# mini-v1_5-moving-parts.net
KiCad netlist of a schematic drawn in EAGLE
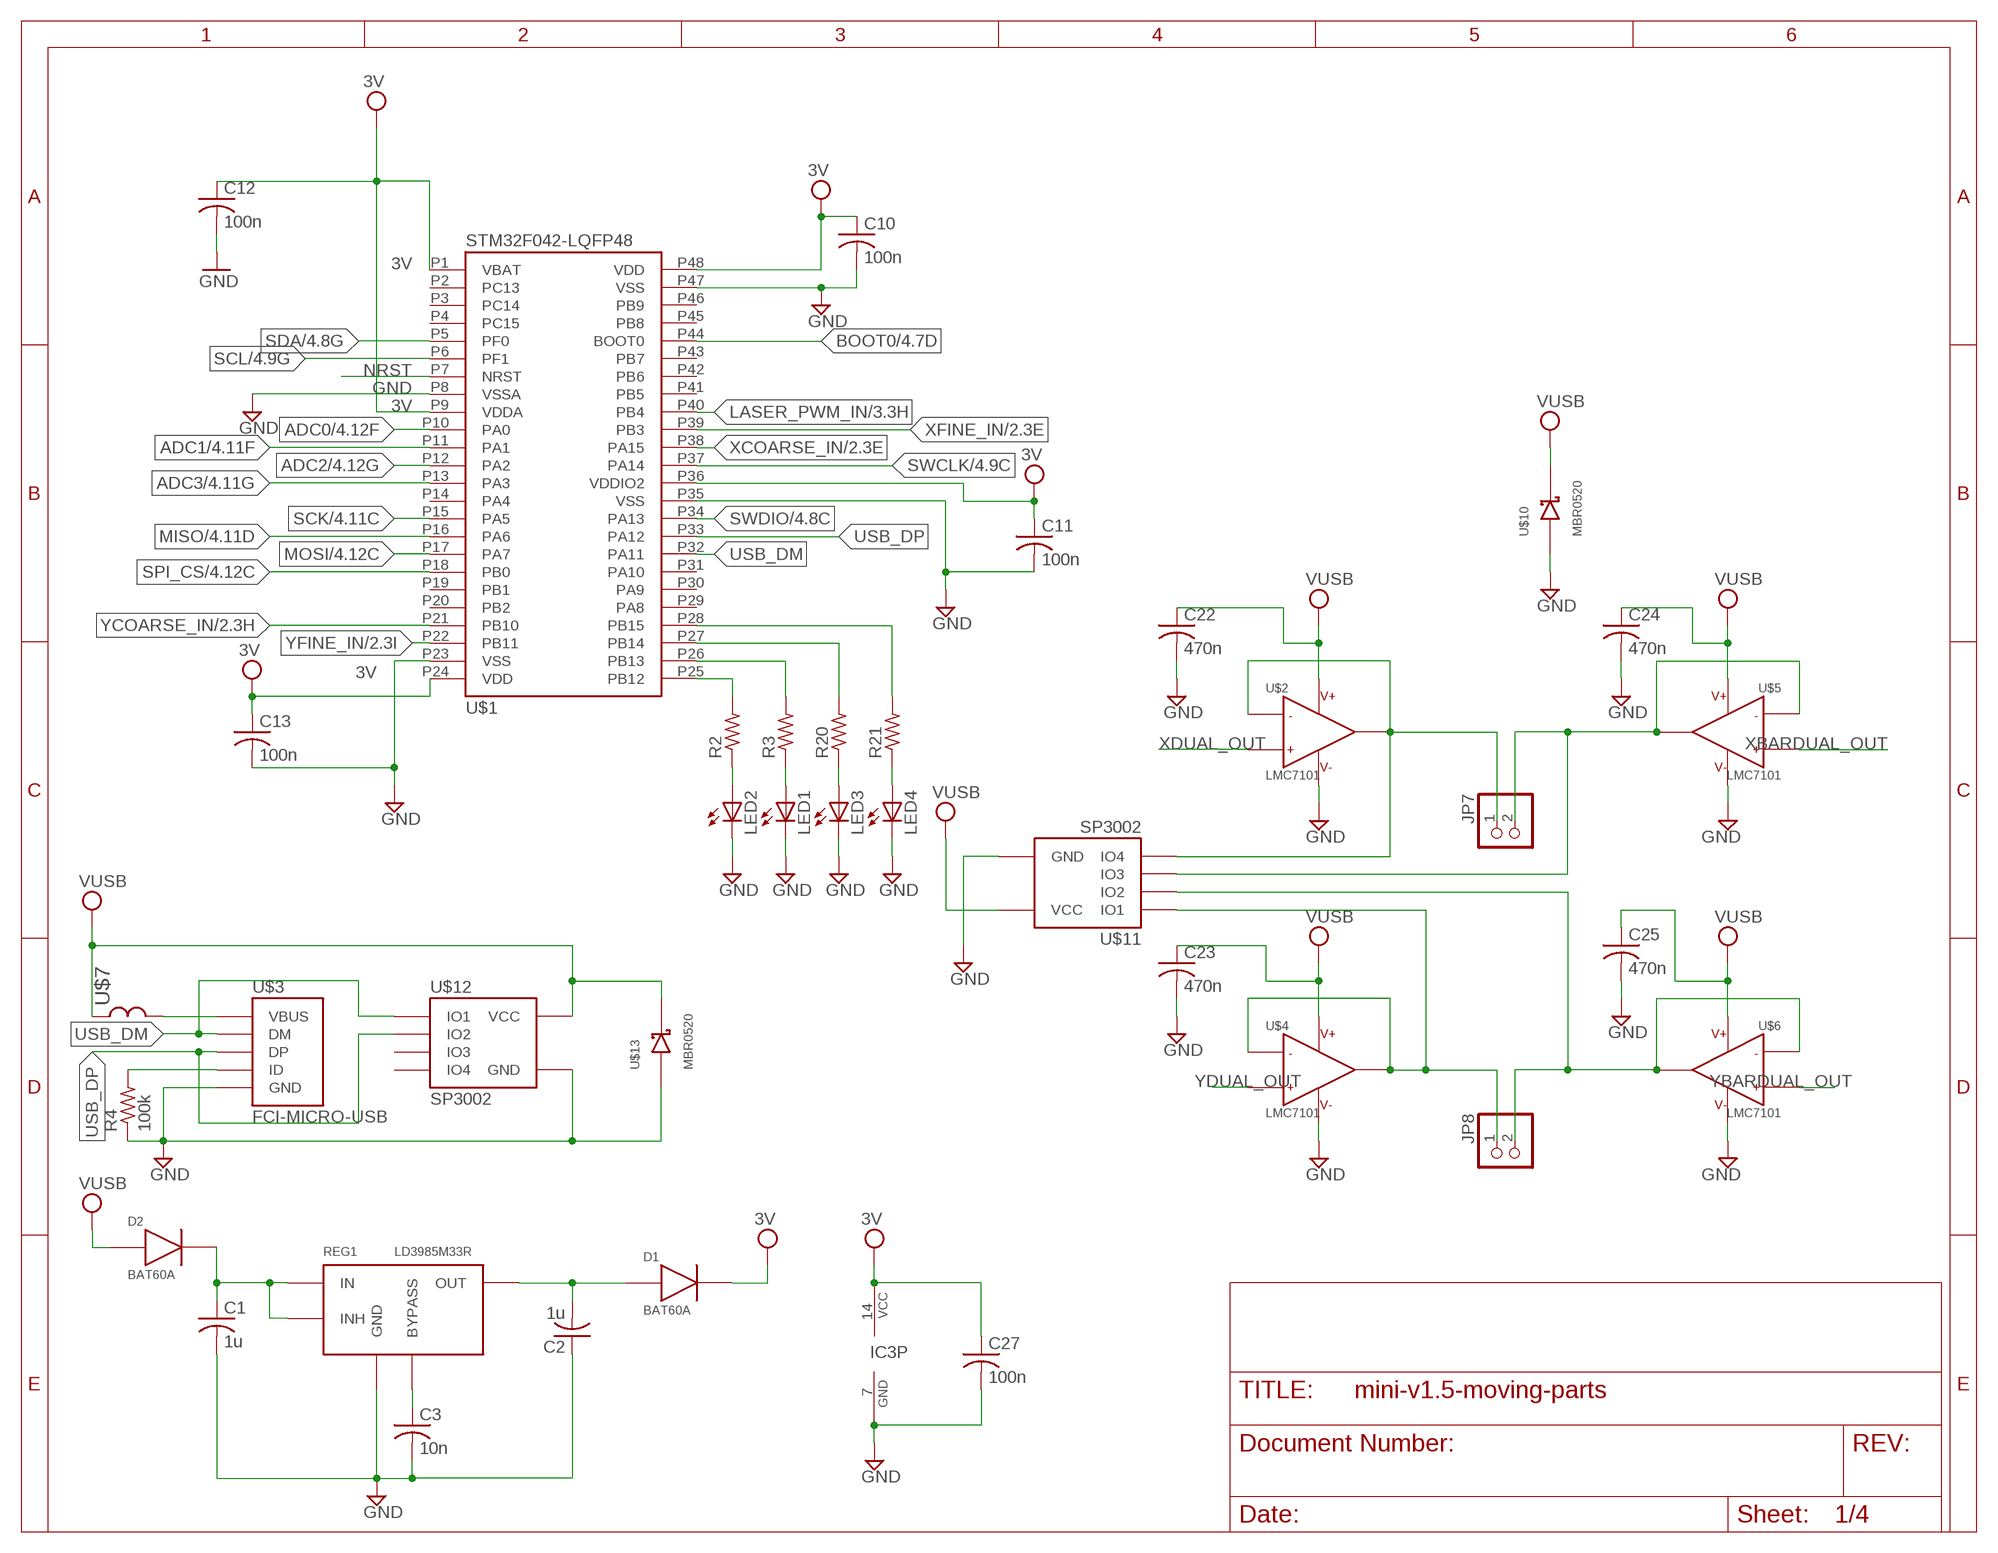
[diagram p0: schematic, sheet 1]
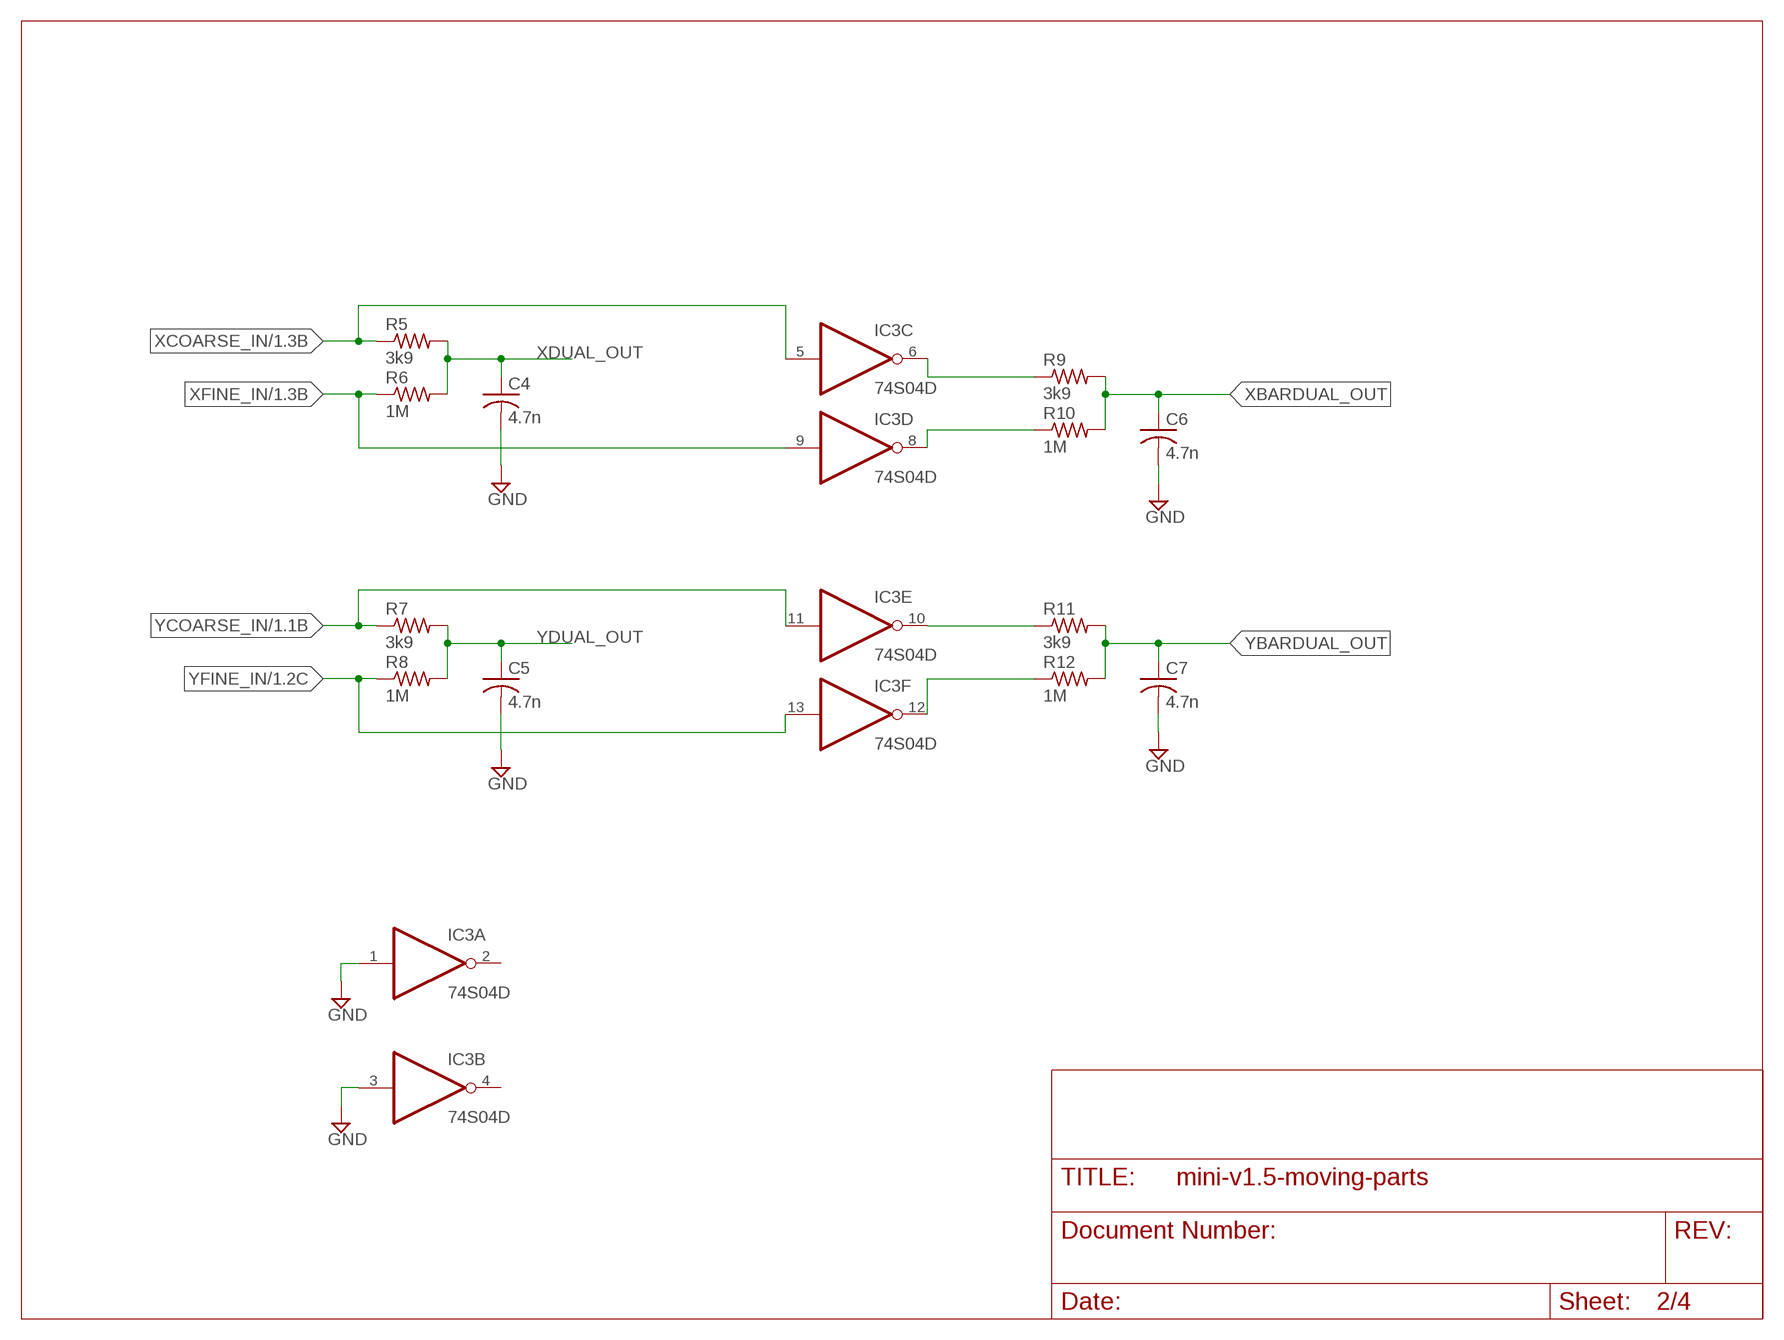
[diagram p1: schematic, sheet 2]
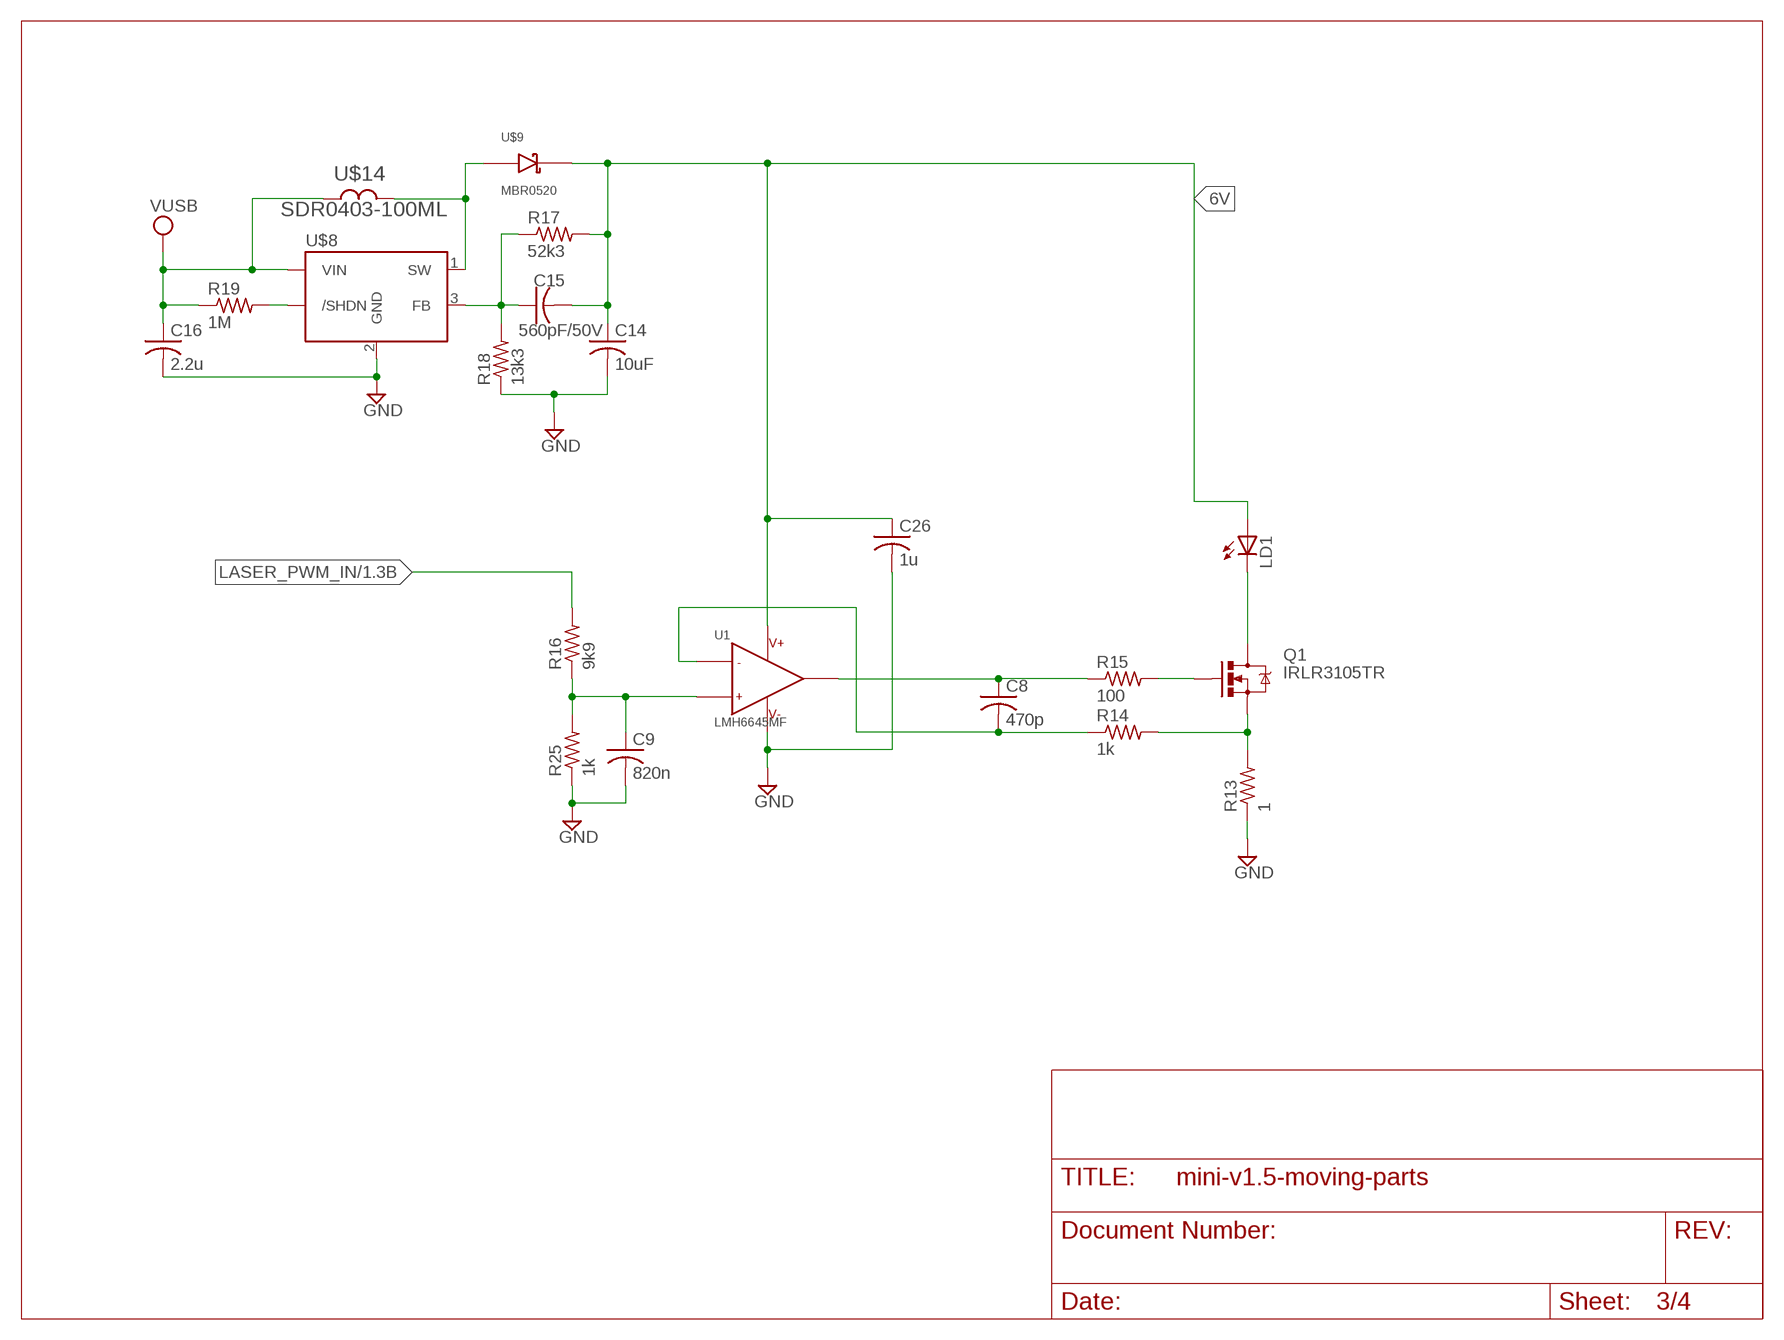
[diagram p2: schematic, sheet 3]
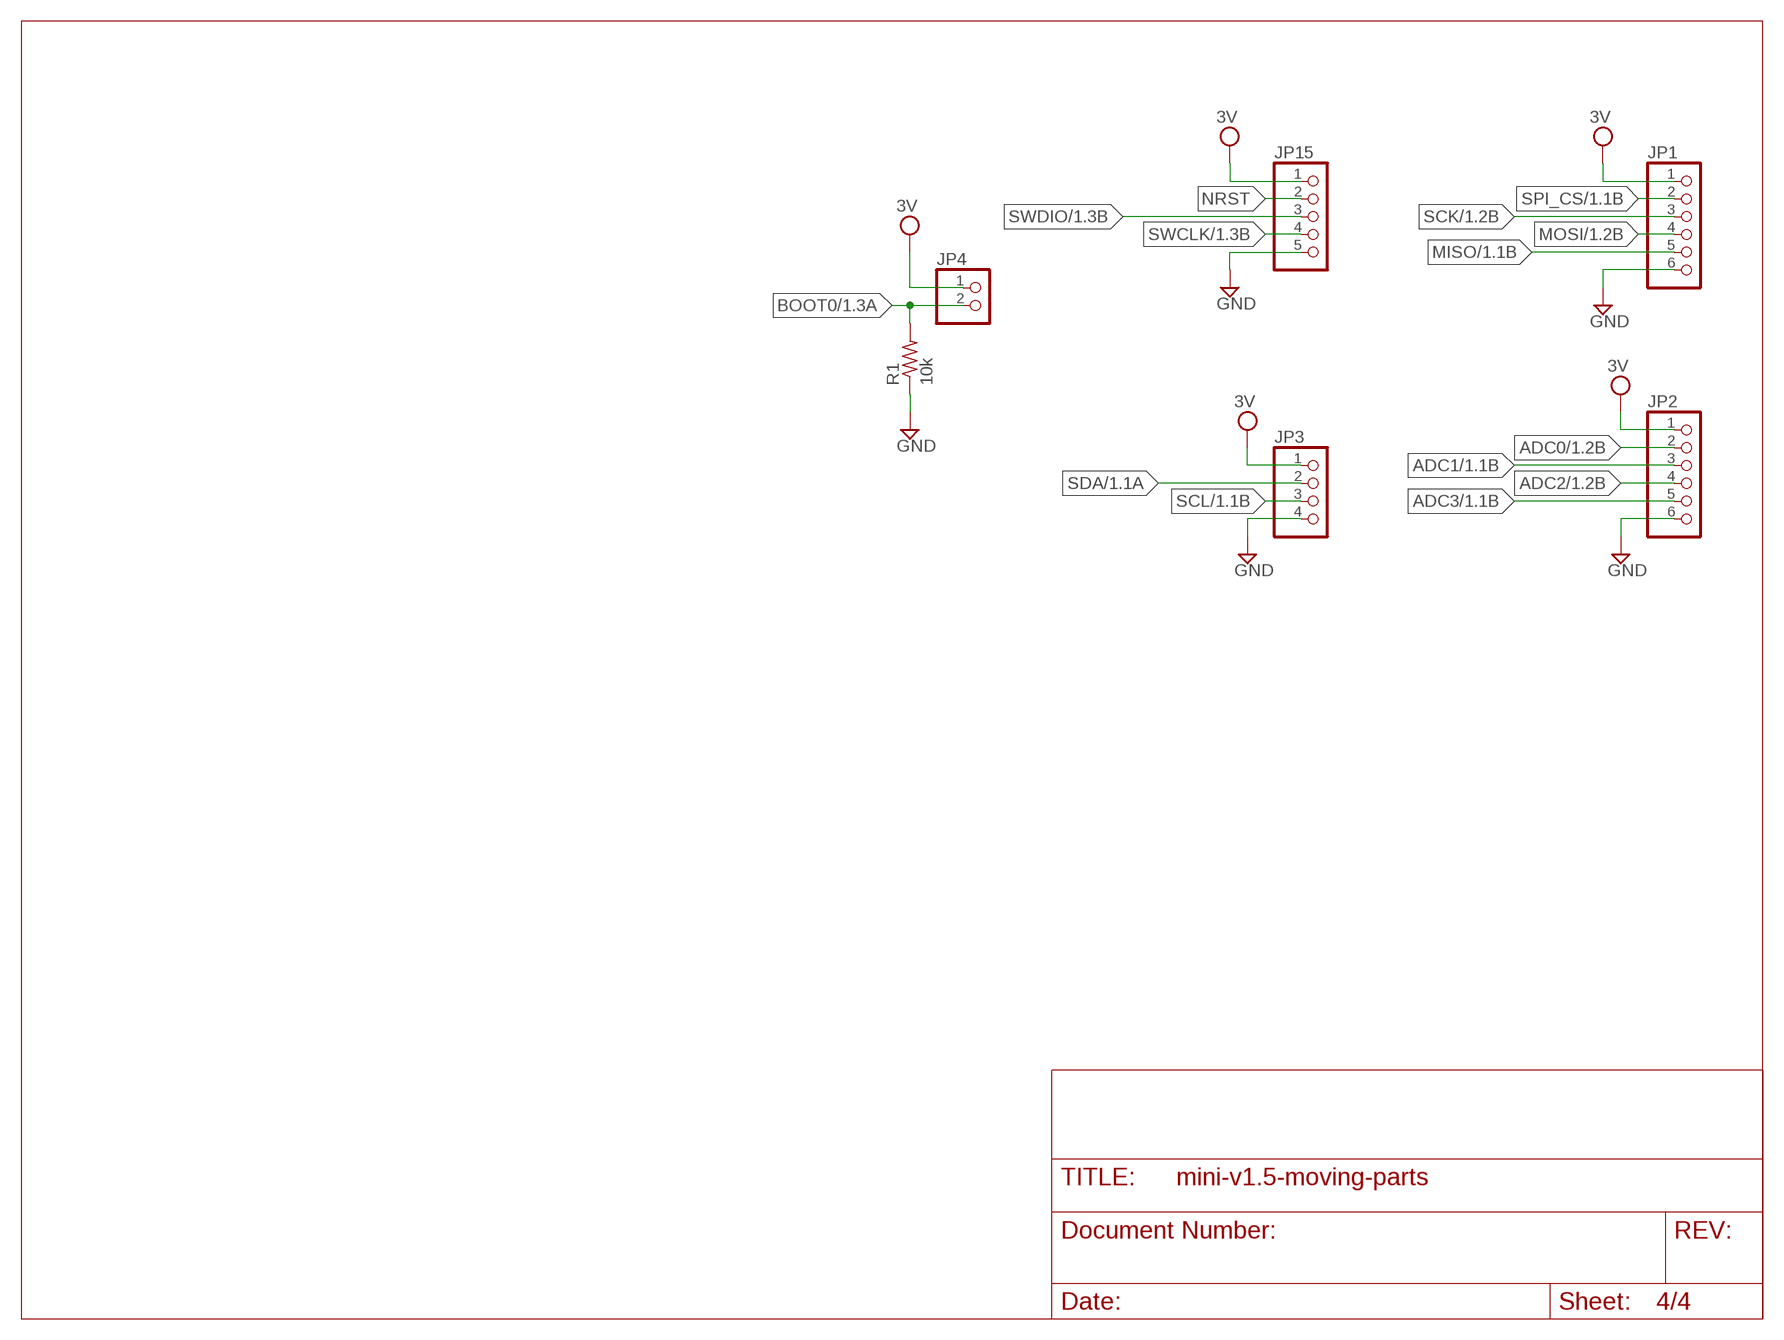
[diagram p3: schematic, sheet 4]

(export (version "E")
  (design (tool "Eeschema 10.0.6"))
  (components
    (comp (ref "C1")
      (value "1u")
      (footprint "eagle-import:C0603")
      (libsource (lib "eagle-import") (part "C-USC0603"))
    )
    (comp (ref "C2")
      (value "1u")
      (footprint "eagle-import:C0603")
      (libsource (lib "eagle-import") (part "C-USC0603"))
    )
    (comp (ref "C3")
      (value "10n")
      (footprint "eagle-import:C0603")
      (libsource (lib "eagle-import") (part "C-USC0603"))
    )
    (comp (ref "C10")
      (value "100n")
      (footprint "eagle-import:C0603")
      (libsource (lib "eagle-import") (part "C-USC0603"))
    )
    (comp (ref "C11")
      (value "100n")
      (footprint "eagle-import:C0603")
      (libsource (lib "eagle-import") (part "C-USC0603"))
    )
    (comp (ref "C12")
      (value "100n")
      (footprint "eagle-import:C0603")
      (libsource (lib "eagle-import") (part "C-USC0603"))
    )
    (comp (ref "C13")
      (value "100n")
      (footprint "eagle-import:C0603")
      (libsource (lib "eagle-import") (part "C-USC0603"))
    )
    (comp (ref "C22")
      (value "470n")
      (footprint "eagle-import:C0603")
      (libsource (lib "eagle-import") (part "C-USC0603"))
    )
    (comp (ref "C23")
      (value "470n")
      (footprint "eagle-import:C0603")
      (libsource (lib "eagle-import") (part "C-USC0603"))
    )
    (comp (ref "C24")
      (value "470n")
      (footprint "eagle-import:C0603")
      (libsource (lib "eagle-import") (part "C-USC0603"))
    )
    (comp (ref "C25")
      (value "470n")
      (footprint "eagle-import:C0603")
      (libsource (lib "eagle-import") (part "C-USC0603"))
    )
    (comp (ref "C27")
      (value "100n")
      (footprint "eagle-import:C0603")
      (libsource (lib "eagle-import") (part "C-USC0603"))
    )
    (comp (ref "D1")
      (value "BAT60A")
      (footprint "eagle-import:SOD323")
      (libsource (lib "eagle-import") (part "BAT60A"))
    )
    (comp (ref "D2")
      (value "BAT60A")
      (footprint "eagle-import:SOD323")
      (libsource (lib "eagle-import") (part "BAT60A"))
    )
    (comp (ref "IC3")
      (value "74S04D")
      (footprint "eagle-import:SO14")
      (libsource (lib "eagle-import") (part "7404DS"))
    )
    (comp (ref "JP7")
      (value "PINHD-1X2")
      (footprint "eagle-import:1X02")
      (libsource (lib "eagle-import") (part "PINHD-1X2"))
    )
    (comp (ref "JP8")
      (value "PINHD-1X2")
      (footprint "eagle-import:1X02")
      (libsource (lib "eagle-import") (part "PINHD-1X2"))
    )
    (comp (ref "LED1")
      (value "LEDCHIP-LED0603")
      (footprint "eagle-import:CHIP-LED0603")
      (libsource (lib "eagle-import") (part "LEDCHIP-LED0603"))
    )
    (comp (ref "LED2")
      (value "LEDCHIP-LED0603")
      (footprint "eagle-import:CHIP-LED0603")
      (libsource (lib "eagle-import") (part "LEDCHIP-LED0603"))
    )
    (comp (ref "LED3")
      (value "LEDCHIP-LED0603")
      (footprint "eagle-import:CHIP-LED0603")
      (libsource (lib "eagle-import") (part "LEDCHIP-LED0603"))
    )
    (comp (ref "LED4")
      (value "LEDCHIP-LED0603")
      (footprint "eagle-import:CHIP-LED0603")
      (libsource (lib "eagle-import") (part "LEDCHIP-LED0603"))
    )
    (comp (ref "R2")
      (value "R-US_R0603")
      (footprint "eagle-import:R0603")
      (libsource (lib "eagle-import") (part "R-US_R0603"))
    )
    (comp (ref "R3")
      (value "R-US_R0603")
      (footprint "eagle-import:R0603")
      (libsource (lib "eagle-import") (part "R-US_R0603"))
    )
    (comp (ref "R4")
      (value "100k")
      (footprint "eagle-import:R0603")
      (libsource (lib "eagle-import") (part "R-US_R0603"))
    )
    (comp (ref "R20")
      (value "R-US_R0603")
      (footprint "eagle-import:R0603")
      (libsource (lib "eagle-import") (part "R-US_R0603"))
    )
    (comp (ref "R21")
      (value "R-US_R0603")
      (footprint "eagle-import:R0603")
      (libsource (lib "eagle-import") (part "R-US_R0603"))
    )
    (comp (ref "REG1")
      (value "LD3985M33R")
      (footprint "eagle-import:SOT23-5L")
      (libsource (lib "eagle-import") (part "LD3985MXXR"))
    )
    (comp (ref "U$1")
      (value "STM32F042-LQFP48")
      (footprint "eagle-import:LQFP48")
      (libsource (lib "eagle-import") (part "STM32F042-LQFP48"))
    )
    (comp (ref "U$2")
      (value "LMC7101")
      (footprint "eagle-import:SOT23-5")
      (libsource (lib "eagle-import") (part "LMC7101"))
    )
    (comp (ref "U$3")
      (value "FCI-MICRO-USB")
      (footprint "eagle-import:FCI-MICROUSB")
      (libsource (lib "eagle-import") (part "FCI-MICRO-USB"))
    )
    (comp (ref "U$4")
      (value "LMC7101")
      (footprint "eagle-import:SOT23-5")
      (libsource (lib "eagle-import") (part "LMC7101"))
    )
    (comp (ref "U$5")
      (value "LMC7101")
      (footprint "eagle-import:SOT23-5")
      (libsource (lib "eagle-import") (part "LMC7101"))
    )
    (comp (ref "U$6")
      (value "LMC7101")
      (footprint "eagle-import:SOT23-5")
      (libsource (lib "eagle-import") (part "LMC7101"))
    )
    (comp (ref "U$7")
      (value "L_TDK_1005")
      (footprint "eagle-import:MLK1005")
      (libsource (lib "eagle-import") (part "L_TDK_1005"))
    )
    (comp (ref "U$10")
      (value "MBR0520")
      (footprint "eagle-import:SOD123")
      (libsource (lib "eagle-import") (part "MBR0520"))
    )
    (comp (ref "U$11")
      (value "SP3002")
      (footprint "eagle-import:SC70-6")
      (libsource (lib "eagle-import") (part "SP3002"))
    )
    (comp (ref "U$12")
      (value "SP3002")
      (footprint "eagle-import:SC70-6")
      (libsource (lib "eagle-import") (part "SP3002"))
    )
    (comp (ref "U$13")
      (value "MBR0520")
      (footprint "eagle-import:SOD123")
      (libsource (lib "eagle-import") (part "MBR0520"))
    )
    (comp (ref "C4")
      (value "4.7n")
      (footprint "eagle-import:C0603")
      (libsource (lib "eagle-import") (part "C-USC0603"))
    )
    (comp (ref "C5")
      (value "4.7n")
      (footprint "eagle-import:C0603")
      (libsource (lib "eagle-import") (part "C-USC0603"))
    )
    (comp (ref "C6")
      (value "4.7n")
      (footprint "eagle-import:C0603")
      (libsource (lib "eagle-import") (part "C-USC0603"))
    )
    (comp (ref "C7")
      (value "4.7n")
      (footprint "eagle-import:C0603")
      (libsource (lib "eagle-import") (part "C-USC0603"))
    )
    (comp (ref "R5")
      (value "3k9")
      (footprint "eagle-import:R0603")
      (libsource (lib "eagle-import") (part "R-US_R0603"))
    )
    (comp (ref "R6")
      (value "1M")
      (footprint "eagle-import:R0603")
      (libsource (lib "eagle-import") (part "R-US_R0603"))
    )
    (comp (ref "R7")
      (value "3k9")
      (footprint "eagle-import:R0603")
      (libsource (lib "eagle-import") (part "R-US_R0603"))
    )
    (comp (ref "R8")
      (value "1M")
      (footprint "eagle-import:R0603")
      (libsource (lib "eagle-import") (part "R-US_R0603"))
    )
    (comp (ref "R9")
      (value "3k9")
      (footprint "eagle-import:R0603")
      (libsource (lib "eagle-import") (part "R-US_R0603"))
    )
    (comp (ref "R10")
      (value "1M")
      (footprint "eagle-import:R0603")
      (libsource (lib "eagle-import") (part "R-US_R0603"))
    )
    (comp (ref "R11")
      (value "3k9")
      (footprint "eagle-import:R0603")
      (libsource (lib "eagle-import") (part "R-US_R0603"))
    )
    (comp (ref "R12")
      (value "1M")
      (footprint "eagle-import:R0603")
      (libsource (lib "eagle-import") (part "R-US_R0603"))
    )
    (comp (ref "C8")
      (value "470p")
      (footprint "eagle-import:C0603")
      (libsource (lib "eagle-import") (part "C-USC0603"))
    )
    (comp (ref "C9")
      (value "820n")
      (footprint "eagle-import:C0603")
      (libsource (lib "eagle-import") (part "C-USC0603"))
    )
    (comp (ref "C14")
      (value "10uF")
      (footprint "eagle-import:C0603")
      (libsource (lib "eagle-import") (part "C-USC0603"))
    )
    (comp (ref "C15")
      (value "560pF/50V")
      (footprint "eagle-import:C0603")
      (libsource (lib "eagle-import") (part "C-USC0603"))
    )
    (comp (ref "C16")
      (value "2.2u")
      (footprint "eagle-import:C0603")
      (libsource (lib "eagle-import") (part "C-USC0603"))
    )
    (comp (ref "C26")
      (value "1u")
      (footprint "eagle-import:C0603")
      (libsource (lib "eagle-import") (part "C-USC0603"))
    )
    (comp (ref "LD1")
      (value "LASERDIODELD2")
      (footprint "eagle-import:LASERDIODE2")
      (fields (field (name "MPN") "3 x (0552-2-15-15-11-27-10-0)"))
      (libsource (lib "eagle-import") (part "LASERDIODELD2"))
    )
    (comp (ref "Q1")
      (value "IRLR3105TR")
      (footprint "eagle-import:DPAK")
      (libsource (lib "eagle-import") (part "FET-N-IRLR3105TRIRLR3105TR"))
    )
    (comp (ref "R13")
      (value "1")
      (footprint "eagle-import:R0603")
      (libsource (lib "eagle-import") (part "R-US_R0603"))
    )
    (comp (ref "R14")
      (value "1k")
      (footprint "eagle-import:R0603")
      (libsource (lib "eagle-import") (part "R-US_R0603"))
    )
    (comp (ref "R15")
      (value "100")
      (footprint "eagle-import:R0603")
      (libsource (lib "eagle-import") (part "R-US_R0603"))
    )
    (comp (ref "R16")
      (value "9k9")
      (footprint "eagle-import:R0603")
      (libsource (lib "eagle-import") (part "R-US_R0603"))
    )
    (comp (ref "R17")
      (value "52k3")
      (footprint "eagle-import:R0603")
      (libsource (lib "eagle-import") (part "R-US_R0603"))
    )
    (comp (ref "R18")
      (value "13k3")
      (footprint "eagle-import:R0603")
      (libsource (lib "eagle-import") (part "R-US_R0603"))
    )
    (comp (ref "R19")
      (value "1M")
      (footprint "eagle-import:R0603")
      (libsource (lib "eagle-import") (part "R-US_R0603"))
    )
    (comp (ref "R25")
      (value "1k")
      (footprint "eagle-import:R0603")
      (libsource (lib "eagle-import") (part "R-US_R0603"))
    )
    (comp (ref "U$8")
      (value "LMR62014")
      (footprint "eagle-import:SOT23-5")
      (libsource (lib "eagle-import") (part "LMR62014"))
    )
    (comp (ref "U$9")
      (value "MBR0520")
      (footprint "eagle-import:SOD123")
      (libsource (lib "eagle-import") (part "MBR0520"))
    )
    (comp (ref "U$14")
      (value "SDR0403-100ML")
      (footprint "eagle-import:SDR0403")
      (libsource (lib "eagle-import") (part "SDR0403"))
    )
    (comp (ref "U1")
      (value "LMH6645MF")
      (footprint "eagle-import:SOT23-5")
      (libsource (lib "eagle-import") (part "OPAMP-SINGLELMH6645MF"))
    )
    (comp (ref "JP1")
      (value "PINHD-1X6")
      (footprint "eagle-import:1X06")
      (libsource (lib "eagle-import") (part "PINHD-1X6"))
    )
    (comp (ref "JP2")
      (value "PINHD-1X6")
      (footprint "eagle-import:1X06")
      (libsource (lib "eagle-import") (part "PINHD-1X6"))
    )
    (comp (ref "JP3")
      (value "PINHD-1X4")
      (footprint "eagle-import:1X04")
      (libsource (lib "eagle-import") (part "PINHD-1X4"))
    )
    (comp (ref "JP4")
      (value "PINHD-1X2")
      (footprint "eagle-import:1X02")
      (libsource (lib "eagle-import") (part "PINHD-1X2"))
    )
    (comp (ref "JP15")
      (value "PINHD-1X5")
      (footprint "eagle-import:1X05")
      (libsource (lib "eagle-import") (part "PINHD-1X5"))
    )
    (comp (ref "R1")
      (value "10k")
      (footprint "eagle-import:R0603")
      (libsource (lib "eagle-import") (part "R-US_R0603"))
    )
  )
  (nets
    (net (code "1") (name "3V") (class "Default")
      (node (ref "C10") (pin "1") (pinfunction "1_1") (pintype "passive"))
      (node (ref "C11") (pin "1") (pinfunction "1_1") (pintype "passive"))
      (node (ref "C12") (pin "1") (pinfunction "1_1") (pintype "passive"))
      (node (ref "C13") (pin "1") (pinfunction "1_1") (pintype "passive"))
      (node (ref "C27") (pin "1") (pinfunction "1_1") (pintype "passive"))
      (node (ref "D1") (pin "1") (pinfunction "1_1") (pintype "bidirectional"))
      (node (ref "IC3") (pin "14") (pinfunction "VCC_14") (pintype "power_in"))
      (node (ref "JP1") (pin "1") (pinfunction "1_1") (pintype "passive"))
      (node (ref "JP15") (pin "1") (pinfunction "1_1") (pintype "passive"))
      (node (ref "JP2") (pin "1") (pinfunction "1_1") (pintype "passive"))
      (node (ref "JP3") (pin "1") (pinfunction "1_1") (pintype "passive"))
      (node (ref "JP4") (pin "1") (pinfunction "1_1") (pintype "passive"))
      (node (ref "U$1") (pin "P1") (pinfunction "VBAT_P1") (pintype "bidirectional"))
      (node (ref "U$1") (pin "P24") (pinfunction "VDD_P24") (pintype "bidirectional"))
      (node (ref "U$1") (pin "P36") (pinfunction "VDDIO2_P36") (pintype "bidirectional"))
      (node (ref "U$1") (pin "P48") (pinfunction "VDD_P48") (pintype "bidirectional"))
      (node (ref "U$1") (pin "P9") (pinfunction "VDDA_P9") (pintype "bidirectional"))
    )
    (net (code "2") (name "6V") (class "Default")
      (node (ref "C14") (pin "1") (pinfunction "1_1") (pintype "passive"))
      (node (ref "C15") (pin "2") (pinfunction "2_2") (pintype "passive"))
      (node (ref "C26") (pin "1") (pinfunction "1_1") (pintype "passive"))
      (node (ref "LD1") (pin "P$1") (pinfunction "A_P$1") (pintype "passive"))
      (node (ref "R17") (pin "2") (pinfunction "2_2") (pintype "passive"))
      (node (ref "U$9") (pin "CATHODE") (pinfunction "CATHODE_CATHODE") (pintype "bidirectional"))
      (node (ref "U1") (pin "5") (pinfunction "V+_5") (pintype "power_in"))
    )
    (net (code "3") (name "ADC0") (class "Default")
      (node (ref "JP2") (pin "2") (pinfunction "2_2") (pintype "passive"))
      (node (ref "U$1") (pin "P10") (pinfunction "PA0_P10") (pintype "bidirectional"))
    )
    (net (code "4") (name "ADC1") (class "Default")
      (node (ref "JP2") (pin "3") (pinfunction "3_3") (pintype "passive"))
      (node (ref "U$1") (pin "P11") (pinfunction "PA1_P11") (pintype "bidirectional"))
    )
    (net (code "5") (name "ADC2") (class "Default")
      (node (ref "JP2") (pin "4") (pinfunction "4_4") (pintype "passive"))
      (node (ref "U$1") (pin "P12") (pinfunction "PA2_P12") (pintype "bidirectional"))
    )
    (net (code "6") (name "ADC3") (class "Default")
      (node (ref "JP2") (pin "5") (pinfunction "5_5") (pintype "passive"))
      (node (ref "U$1") (pin "P13") (pinfunction "PA3_P13") (pintype "bidirectional"))
    )
    (net (code "7") (name "BOOT0") (class "Default")
      (node (ref "JP4") (pin "2") (pinfunction "2_2") (pintype "passive"))
      (node (ref "R1") (pin "2") (pinfunction "2_2") (pintype "passive"))
      (node (ref "U$1") (pin "P44") (pinfunction "BOOT0_P44") (pintype "bidirectional"))
    )
    (net (code "8") (name "GND") (class "Default")
      (node (ref "C1") (pin "2") (pinfunction "2_2") (pintype "passive"))
      (node (ref "C10") (pin "2") (pinfunction "2_2") (pintype "passive"))
      (node (ref "C11") (pin "2") (pinfunction "2_2") (pintype "passive"))
      (node (ref "C12") (pin "2") (pinfunction "2_2") (pintype "passive"))
      (node (ref "C13") (pin "2") (pinfunction "2_2") (pintype "passive"))
      (node (ref "C14") (pin "2") (pinfunction "2_2") (pintype "passive"))
      (node (ref "C16") (pin "2") (pinfunction "2_2") (pintype "passive"))
      (node (ref "C2") (pin "1") (pinfunction "1_1") (pintype "passive"))
      (node (ref "C22") (pin "2") (pinfunction "2_2") (pintype "passive"))
      (node (ref "C23") (pin "2") (pinfunction "2_2") (pintype "passive"))
      (node (ref "C24") (pin "2") (pinfunction "2_2") (pintype "passive"))
      (node (ref "C25") (pin "2") (pinfunction "2_2") (pintype "passive"))
      (node (ref "C26") (pin "2") (pinfunction "2_2") (pintype "passive"))
      (node (ref "C27") (pin "2") (pinfunction "2_2") (pintype "passive"))
      (node (ref "C3") (pin "2") (pinfunction "2_2") (pintype "passive"))
      (node (ref "C4") (pin "2") (pinfunction "2_2") (pintype "passive"))
      (node (ref "C5") (pin "2") (pinfunction "2_2") (pintype "passive"))
      (node (ref "C6") (pin "2") (pinfunction "2_2") (pintype "passive"))
      (node (ref "C7") (pin "2") (pinfunction "2_2") (pintype "passive"))
      (node (ref "C9") (pin "2") (pinfunction "2_2") (pintype "passive"))
      (node (ref "IC3") (pin "1") (pinfunction "I_1") (pintype "input"))
      (node (ref "IC3") (pin "3") (pinfunction "I_3") (pintype "input"))
      (node (ref "IC3") (pin "7") (pinfunction "GND_7") (pintype "power_in"))
      (node (ref "JP1") (pin "6") (pinfunction "6_6") (pintype "passive"))
      (node (ref "JP15") (pin "5") (pinfunction "5_5") (pintype "passive"))
      (node (ref "JP2") (pin "6") (pinfunction "6_6") (pintype "passive"))
      (node (ref "JP3") (pin "4") (pinfunction "4_4") (pintype "passive"))
      (node (ref "LED1") (pin "C") (pinfunction "C_C") (pintype "passive"))
      (node (ref "LED2") (pin "C") (pinfunction "C_C") (pintype "passive"))
      (node (ref "LED3") (pin "C") (pinfunction "C_C") (pintype "passive"))
      (node (ref "LED4") (pin "C") (pinfunction "C_C") (pintype "passive"))
      (node (ref "R1") (pin "1") (pinfunction "1_1") (pintype "passive"))
      (node (ref "R13") (pin "1") (pinfunction "1_1") (pintype "passive"))
      (node (ref "R18") (pin "1") (pinfunction "1_1") (pintype "passive"))
      (node (ref "R25") (pin "1") (pinfunction "1_1") (pintype "passive"))
      (node (ref "R4") (pin "1") (pinfunction "1_1") (pintype "passive"))
      (node (ref "REG1") (pin "GND") (pinfunction "GND_GND") (pintype "bidirectional"))
      (node (ref "U$1") (pin "P23") (pinfunction "VSS_P23") (pintype "bidirectional"))
      (node (ref "U$1") (pin "P35") (pinfunction "VSS_P35") (pintype "bidirectional"))
      (node (ref "U$1") (pin "P47") (pinfunction "VSS_P47") (pintype "bidirectional"))
      (node (ref "U$1") (pin "P8") (pinfunction "VSSA_P8") (pintype "bidirectional"))
      (node (ref "U$10") (pin "ANODE") (pinfunction "ANODE_ANODE") (pintype "bidirectional"))
      (node (ref "U$11") (pin "P2") (pinfunction "GND_P2") (pintype "power_in"))
      (node (ref "U$12") (pin "P2") (pinfunction "GND_P2") (pintype "power_in"))
      (node (ref "U$13") (pin "ANODE") (pinfunction "ANODE_ANODE") (pintype "bidirectional"))
      (node (ref "U$2") (pin "5") (pinfunction "P5_5") (pintype "power_in"))
      (node (ref "U$3") (pin "P5") (pinfunction "GND_P5") (pintype "bidirectional"))
      (node (ref "U$4") (pin "5") (pinfunction "P5_5") (pintype "power_in"))
      (node (ref "U$5") (pin "5") (pinfunction "P5_5") (pintype "power_in"))
      (node (ref "U$6") (pin "5") (pinfunction "P5_5") (pintype "power_in"))
      (node (ref "U$8") (pin "2") (pinfunction "GND_2") (pintype "bidirectional"))
      (node (ref "U1") (pin "2") (pinfunction "V-_2") (pintype "power_in"))
    )
    (net (code "9") (name "LASER_PWM_IN") (class "Default")
      (node (ref "R16") (pin "2") (pinfunction "2_2") (pintype "passive"))
      (node (ref "U$1") (pin "P40") (pinfunction "PB4_P40") (pintype "bidirectional"))
    )
    (net (code "10") (name "MISO") (class "Default")
      (node (ref "JP1") (pin "5") (pinfunction "5_5") (pintype "passive"))
      (node (ref "U$1") (pin "P16") (pinfunction "PA6_P16") (pintype "bidirectional"))
    )
    (net (code "11") (name "MOSI") (class "Default")
      (node (ref "JP1") (pin "4") (pinfunction "4_4") (pintype "passive"))
      (node (ref "U$1") (pin "P17") (pinfunction "PA7_P17") (pintype "bidirectional"))
    )
    (net (code "12") (name "NRST") (class "Default")
      (node (ref "JP15") (pin "2") (pinfunction "2_2") (pintype "passive"))
      (node (ref "U$1") (pin "P7") (pinfunction "NRST_P7") (pintype "bidirectional"))
    )
    (net (code "13") (name "Net-(C2-Pad2)") (class "Default")
      (node (ref "C2") (pin "2") (pinfunction "2_2") (pintype "passive"))
      (node (ref "D1") (pin "2") (pinfunction "2_2") (pintype "bidirectional"))
      (node (ref "REG1") (pin "OUT") (pinfunction "OUT_OUT") (pintype "bidirectional"))
    )
    (net (code "14") (name "Net-(C3-Pad1)") (class "Default")
      (node (ref "C3") (pin "1") (pinfunction "1_1") (pintype "passive"))
      (node (ref "REG1") (pin "BYPASS") (pinfunction "BYPASS_BYPASS") (pintype "bidirectional"))
    )
    (net (code "15") (name "Net-(IC3C-O)") (class "Default")
      (node (ref "IC3") (pin "6") (pinfunction "O_6") (pintype "output"))
      (node (ref "R9") (pin "1") (pinfunction "1_1") (pintype "passive"))
    )
    (net (code "16") (name "Net-(IC3D-O)") (class "Default")
      (node (ref "IC3") (pin "8") (pinfunction "O_8") (pintype "output"))
      (node (ref "R10") (pin "1") (pinfunction "1_1") (pintype "passive"))
    )
    (net (code "17") (name "Net-(IC3E-O)") (class "Default")
      (node (ref "IC3") (pin "10") (pinfunction "O_10") (pintype "output"))
      (node (ref "R11") (pin "1") (pinfunction "1_1") (pintype "passive"))
    )
    (net (code "18") (name "Net-(IC3F-O)") (class "Default")
      (node (ref "IC3") (pin "12") (pinfunction "O_12") (pintype "output"))
      (node (ref "R12") (pin "1") (pinfunction "1_1") (pintype "passive"))
    )
    (net (code "19") (name "Net-(LD1-C)") (class "Default")
      (node (ref "LD1") (pin "P$3") (pinfunction "C_P$3") (pintype "passive"))
      (node (ref "Q1") (pin "4") (pinfunction "D_4") (pintype "passive"))
    )
    (net (code "20") (name "Net-(LED1-PadA)") (class "Default")
      (node (ref "LED1") (pin "A") (pinfunction "A_A") (pintype "passive"))
      (node (ref "R3") (pin "1") (pinfunction "1_1") (pintype "passive"))
    )
    (net (code "21") (name "Net-(LED2-PadA)") (class "Default")
      (node (ref "LED2") (pin "A") (pinfunction "A_A") (pintype "passive"))
      (node (ref "R2") (pin "1") (pinfunction "1_1") (pintype "passive"))
    )
    (net (code "22") (name "Net-(LED3-PadA)") (class "Default")
      (node (ref "LED3") (pin "A") (pinfunction "A_A") (pintype "passive"))
      (node (ref "R20") (pin "1") (pinfunction "1_1") (pintype "passive"))
    )
    (net (code "23") (name "Net-(LED4-PadA)") (class "Default")
      (node (ref "LED4") (pin "A") (pinfunction "A_A") (pintype "passive"))
      (node (ref "R21") (pin "1") (pinfunction "1_1") (pintype "passive"))
    )
    (net (code "24") (name "Net-(Q1-G)") (class "Default")
      (node (ref "Q1") (pin "1") (pinfunction "G_1") (pintype "passive"))
      (node (ref "R15") (pin "2") (pinfunction "2_2") (pintype "passive"))
    )
    (net (code "25") (name "Net-(Q1-S)") (class "Default")
      (node (ref "Q1") (pin "3") (pinfunction "S_3") (pintype "passive"))
      (node (ref "R13") (pin "2") (pinfunction "2_2") (pintype "passive"))
      (node (ref "R14") (pin "2") (pinfunction "2_2") (pintype "passive"))
    )
    (net (code "26") (name "Net-(REG1-INH)") (class "Default")
      (node (ref "C1") (pin "1") (pinfunction "1_1") (pintype "passive"))
      (node (ref "D2") (pin "1") (pinfunction "1_1") (pintype "bidirectional"))
      (node (ref "REG1") (pin "IN") (pinfunction "IN_IN") (pintype "bidirectional"))
      (node (ref "REG1") (pin "INHIBIT") (pinfunction "INH_INHIBIT") (pintype "bidirectional"))
    )
    (net (code "27") (name "Net-(U$1-PB12)") (class "Default")
      (node (ref "R2") (pin "2") (pinfunction "2_2") (pintype "passive"))
      (node (ref "U$1") (pin "P25") (pinfunction "PB12_P25") (pintype "bidirectional"))
    )
    (net (code "28") (name "Net-(U$1-PB13)") (class "Default")
      (node (ref "R3") (pin "2") (pinfunction "2_2") (pintype "passive"))
      (node (ref "U$1") (pin "P26") (pinfunction "PB13_P26") (pintype "bidirectional"))
    )
    (net (code "29") (name "Net-(U$1-PB14)") (class "Default")
      (node (ref "R20") (pin "2") (pinfunction "2_2") (pintype "passive"))
      (node (ref "U$1") (pin "P27") (pinfunction "PB14_P27") (pintype "bidirectional"))
    )
    (net (code "30") (name "Net-(U$1-PB15)") (class "Default")
      (node (ref "R21") (pin "2") (pinfunction "2_2") (pintype "passive"))
      (node (ref "U$1") (pin "P28") (pinfunction "PB15_P28") (pintype "bidirectional"))
    )
    (net (code "31") (name "Net-(U$3-ID)") (class "Default")
      (node (ref "R4") (pin "2") (pinfunction "2_2") (pintype "passive"))
      (node (ref "U$3") (pin "P4") (pinfunction "ID_P4") (pintype "bidirectional"))
    )
    (net (code "32") (name "Net-(U$3-VBUS)") (class "Default")
      (node (ref "U$3") (pin "P1") (pinfunction "VBUS_P1") (pintype "bidirectional"))
      (node (ref "U$7") (pin "P$2") (pinfunction "P$2_P$2") (pintype "bidirectional"))
    )
    (net (code "33") (name "Net-(U$8-FB)") (class "Default")
      (node (ref "C15") (pin "1") (pinfunction "1_1") (pintype "passive"))
      (node (ref "R17") (pin "1") (pinfunction "1_1") (pintype "passive"))
      (node (ref "R18") (pin "2") (pinfunction "2_2") (pintype "passive"))
      (node (ref "U$8") (pin "3") (pinfunction "FB_3") (pintype "bidirectional"))
    )
    (net (code "34") (name "Net-(U$8-SW)") (class "Default")
      (node (ref "U$14") (pin "P$2") (pinfunction "P$2_P$2") (pintype "bidirectional"))
      (node (ref "U$8") (pin "1") (pinfunction "SW_1") (pintype "bidirectional"))
      (node (ref "U$9") (pin "ANODE") (pinfunction "ANODE_ANODE") (pintype "bidirectional"))
    )
    (net (code "35") (name "Net-(U$8-{slash}SHDN)") (class "Default")
      (node (ref "R19") (pin "2") (pinfunction "2_2") (pintype "passive"))
      (node (ref "U$8") (pin "4") (pinfunction "/SHDN_4") (pintype "bidirectional"))
    )
    (net (code "36") (name "Net-(U$11-IO1)") (class "Default")
      (node (ref "JP8") (pin "1") (pinfunction "1_1") (pintype "passive"))
      (node (ref "U$11") (pin "P1") (pinfunction "IO1_P1") (pintype "bidirectional"))
      (node (ref "U$4") (pin "1") (pinfunction "P1_1") (pintype "bidirectional"))
      (node (ref "U$4") (pin "4") (pinfunction "P4_4") (pintype "bidirectional"))
    )
    (net (code "37") (name "Net-(U$11-IO2)") (class "Default")
      (node (ref "JP8") (pin "2") (pinfunction "2_2") (pintype "passive"))
      (node (ref "U$11") (pin "P3") (pinfunction "IO2_P3") (pintype "bidirectional"))
      (node (ref "U$6") (pin "1") (pinfunction "P1_1") (pintype "bidirectional"))
      (node (ref "U$6") (pin "4") (pinfunction "P4_4") (pintype "bidirectional"))
    )
    (net (code "38") (name "Net-(U$11-IO3)") (class "Default")
      (node (ref "JP7") (pin "2") (pinfunction "2_2") (pintype "passive"))
      (node (ref "U$11") (pin "P4") (pinfunction "IO3_P4") (pintype "bidirectional"))
      (node (ref "U$5") (pin "1") (pinfunction "P1_1") (pintype "bidirectional"))
      (node (ref "U$5") (pin "4") (pinfunction "P4_4") (pintype "bidirectional"))
    )
    (net (code "39") (name "Net-(U$11-IO4)") (class "Default")
      (node (ref "JP7") (pin "1") (pinfunction "1_1") (pintype "passive"))
      (node (ref "U$11") (pin "P6") (pinfunction "IO4_P6") (pintype "bidirectional"))
      (node (ref "U$2") (pin "1") (pinfunction "P1_1") (pintype "bidirectional"))
      (node (ref "U$2") (pin "4") (pinfunction "P4_4") (pintype "bidirectional"))
    )
    (net (code "40") (name "Net-(U1-IN+)") (class "Default")
      (node (ref "C9") (pin "1") (pinfunction "1_1") (pintype "passive"))
      (node (ref "R16") (pin "1") (pinfunction "1_1") (pintype "passive"))
      (node (ref "R25") (pin "2") (pinfunction "2_2") (pintype "passive"))
      (node (ref "U1") (pin "3") (pinfunction "IN+_3") (pintype "bidirectional"))
    )
    (net (code "41") (name "Net-(U1-IN-)") (class "Default")
      (node (ref "C8") (pin "2") (pinfunction "2_2") (pintype "passive"))
      (node (ref "R14") (pin "1") (pinfunction "1_1") (pintype "passive"))
      (node (ref "U1") (pin "4") (pinfunction "IN-_4") (pintype "bidirectional"))
    )
    (net (code "42") (name "Net-(U1-OUT)") (class "Default")
      (node (ref "C8") (pin "1") (pinfunction "1_1") (pintype "passive"))
      (node (ref "R15") (pin "1") (pinfunction "1_1") (pintype "passive"))
      (node (ref "U1") (pin "1") (pinfunction "OUT_1") (pintype "bidirectional"))
    )
    (net (code "43") (name "SCK") (class "Default")
      (node (ref "JP1") (pin "3") (pinfunction "3_3") (pintype "passive"))
      (node (ref "U$1") (pin "P15") (pinfunction "PA5_P15") (pintype "bidirectional"))
    )
    (net (code "44") (name "SCL") (class "Default")
      (node (ref "JP3") (pin "3") (pinfunction "3_3") (pintype "passive"))
      (node (ref "U$1") (pin "P6") (pinfunction "PF1_P6") (pintype "bidirectional"))
    )
    (net (code "45") (name "SDA") (class "Default")
      (node (ref "JP3") (pin "2") (pinfunction "2_2") (pintype "passive"))
      (node (ref "U$1") (pin "P5") (pinfunction "PF0_P5") (pintype "bidirectional"))
    )
    (net (code "46") (name "SPI_CS") (class "Default")
      (node (ref "JP1") (pin "2") (pinfunction "2_2") (pintype "passive"))
      (node (ref "U$1") (pin "P18") (pinfunction "PB0_P18") (pintype "bidirectional"))
    )
    (net (code "47") (name "SWCLK") (class "Default")
      (node (ref "JP15") (pin "4") (pinfunction "4_4") (pintype "passive"))
      (node (ref "U$1") (pin "P37") (pinfunction "PA14_P37") (pintype "bidirectional"))
    )
    (net (code "48") (name "SWDIO") (class "Default")
      (node (ref "JP15") (pin "3") (pinfunction "3_3") (pintype "passive"))
      (node (ref "U$1") (pin "P34") (pinfunction "PA13_P34") (pintype "bidirectional"))
    )
    (net (code "49") (name "USB_DM") (class "Default")
      (node (ref "U$1") (pin "P32") (pinfunction "PA11_P32") (pintype "bidirectional"))
      (node (ref "U$12") (pin "P1") (pinfunction "IO1_P1") (pintype "bidirectional"))
      (node (ref "U$3") (pin "P2") (pinfunction "DM_P2") (pintype "bidirectional"))
    )
    (net (code "50") (name "USB_DP") (class "Default")
      (node (ref "U$1") (pin "P33") (pinfunction "PA12_P33") (pintype "bidirectional"))
      (node (ref "U$12") (pin "P3") (pinfunction "IO2_P3") (pintype "bidirectional"))
      (node (ref "U$3") (pin "P3") (pinfunction "DP_P3") (pintype "bidirectional"))
    )
    (net (code "51") (name "VUSB") (class "Default")
      (node (ref "C16") (pin "1") (pinfunction "1_1") (pintype "passive"))
      (node (ref "C22") (pin "1") (pinfunction "1_1") (pintype "passive"))
      (node (ref "C23") (pin "1") (pinfunction "1_1") (pintype "passive"))
      (node (ref "C24") (pin "1") (pinfunction "1_1") (pintype "passive"))
      (node (ref "C25") (pin "1") (pinfunction "1_1") (pintype "passive"))
      (node (ref "D2") (pin "2") (pinfunction "2_2") (pintype "bidirectional"))
      (node (ref "R19") (pin "1") (pinfunction "1_1") (pintype "passive"))
      (node (ref "U$10") (pin "CATHODE") (pinfunction "CATHODE_CATHODE") (pintype "bidirectional"))
      (node (ref "U$11") (pin "P5") (pinfunction "VCC_P5") (pintype "power_in"))
      (node (ref "U$12") (pin "P5") (pinfunction "VCC_P5") (pintype "power_in"))
      (node (ref "U$13") (pin "CATHODE") (pinfunction "CATHODE_CATHODE") (pintype "bidirectional"))
      (node (ref "U$14") (pin "P$1") (pinfunction "P$1_P$1") (pintype "bidirectional"))
      (node (ref "U$2") (pin "2") (pinfunction "P2_2") (pintype "power_in"))
      (node (ref "U$4") (pin "2") (pinfunction "P2_2") (pintype "power_in"))
      (node (ref "U$5") (pin "2") (pinfunction "P2_2") (pintype "power_in"))
      (node (ref "U$6") (pin "2") (pinfunction "P2_2") (pintype "power_in"))
      (node (ref "U$7") (pin "P$1") (pinfunction "P$1_P$1") (pintype "bidirectional"))
      (node (ref "U$8") (pin "5") (pinfunction "VIN_5") (pintype "bidirectional"))
    )
    (net (code "52") (name "XBARDUAL_OUT") (class "Default")
      (node (ref "C6") (pin "1") (pinfunction "1_1") (pintype "passive"))
      (node (ref "R10") (pin "2") (pinfunction "2_2") (pintype "passive"))
      (node (ref "R9") (pin "2") (pinfunction "2_2") (pintype "passive"))
      (node (ref "U$5") (pin "3") (pinfunction "P3_3") (pintype "bidirectional"))
    )
    (net (code "53") (name "XCOARSE_IN") (class "Default")
      (node (ref "IC3") (pin "5") (pinfunction "I_5") (pintype "input"))
      (node (ref "R5") (pin "1") (pinfunction "1_1") (pintype "passive"))
      (node (ref "U$1") (pin "P38") (pinfunction "PA15_P38") (pintype "bidirectional"))
    )
    (net (code "54") (name "XDUAL_OUT") (class "Default")
      (node (ref "C4") (pin "1") (pinfunction "1_1") (pintype "passive"))
      (node (ref "R5") (pin "2") (pinfunction "2_2") (pintype "passive"))
      (node (ref "R6") (pin "2") (pinfunction "2_2") (pintype "passive"))
      (node (ref "U$2") (pin "3") (pinfunction "P3_3") (pintype "bidirectional"))
    )
    (net (code "55") (name "XFINE_IN") (class "Default")
      (node (ref "IC3") (pin "9") (pinfunction "I_9") (pintype "input"))
      (node (ref "R6") (pin "1") (pinfunction "1_1") (pintype "passive"))
      (node (ref "U$1") (pin "P39") (pinfunction "PB3_P39") (pintype "bidirectional"))
    )
    (net (code "56") (name "YBARDUAL_OUT") (class "Default")
      (node (ref "C7") (pin "1") (pinfunction "1_1") (pintype "passive"))
      (node (ref "R11") (pin "2") (pinfunction "2_2") (pintype "passive"))
      (node (ref "R12") (pin "2") (pinfunction "2_2") (pintype "passive"))
      (node (ref "U$6") (pin "3") (pinfunction "P3_3") (pintype "bidirectional"))
    )
    (net (code "57") (name "YCOARSE_IN") (class "Default")
      (node (ref "IC3") (pin "11") (pinfunction "I_11") (pintype "input"))
      (node (ref "R7") (pin "1") (pinfunction "1_1") (pintype "passive"))
      (node (ref "U$1") (pin "P21") (pinfunction "PB10_P21") (pintype "bidirectional"))
    )
    (net (code "58") (name "YDUAL_OUT") (class "Default")
      (node (ref "C5") (pin "1") (pinfunction "1_1") (pintype "passive"))
      (node (ref "R7") (pin "2") (pinfunction "2_2") (pintype "passive"))
      (node (ref "R8") (pin "2") (pinfunction "2_2") (pintype "passive"))
      (node (ref "U$4") (pin "3") (pinfunction "P3_3") (pintype "bidirectional"))
    )
    (net (code "59") (name "YFINE_IN") (class "Default")
      (node (ref "IC3") (pin "13") (pinfunction "I_13") (pintype "input"))
      (node (ref "R8") (pin "1") (pinfunction "1_1") (pintype "passive"))
      (node (ref "U$1") (pin "P22") (pinfunction "PB11_P22") (pintype "bidirectional"))
    )
    (net (code "60") (name "unconnected-(IC3A-O-Pad2)") (class "Default")
      (node (ref "IC3") (pin "2") (pinfunction "O_2") (pintype "output"))
    )
    (net (code "61") (name "unconnected-(IC3B-O-Pad4)") (class "Default")
      (node (ref "IC3") (pin "4") (pinfunction "O_4") (pintype "output"))
    )
    (net (code "62") (name "unconnected-(U$1-PA4-PadP14)") (class "Default")
      (node (ref "U$1") (pin "P14") (pinfunction "PA4_P14") (pintype "bidirectional"))
    )
    (net (code "63") (name "unconnected-(U$1-PA8-PadP29)") (class "Default")
      (node (ref "U$1") (pin "P29") (pinfunction "PA8_P29") (pintype "bidirectional"))
    )
    (net (code "64") (name "unconnected-(U$1-PA9-PadP30)") (class "Default")
      (node (ref "U$1") (pin "P30") (pinfunction "PA9_P30") (pintype "bidirectional"))
    )
    (net (code "65") (name "unconnected-(U$1-PA10-PadP31)") (class "Default")
      (node (ref "U$1") (pin "P31") (pinfunction "PA10_P31") (pintype "bidirectional"))
    )
    (net (code "66") (name "unconnected-(U$1-PB1-PadP19)") (class "Default")
      (node (ref "U$1") (pin "P19") (pinfunction "PB1_P19") (pintype "bidirectional"))
    )
    (net (code "67") (name "unconnected-(U$1-PB2-PadP20)") (class "Default")
      (node (ref "U$1") (pin "P20") (pinfunction "PB2_P20") (pintype "bidirectional"))
    )
    (net (code "68") (name "unconnected-(U$1-PB5-PadP41)") (class "Default")
      (node (ref "U$1") (pin "P41") (pinfunction "PB5_P41") (pintype "bidirectional"))
    )
    (net (code "69") (name "unconnected-(U$1-PB6-PadP42)") (class "Default")
      (node (ref "U$1") (pin "P42") (pinfunction "PB6_P42") (pintype "bidirectional"))
    )
    (net (code "70") (name "unconnected-(U$1-PB7-PadP43)") (class "Default")
      (node (ref "U$1") (pin "P43") (pinfunction "PB7_P43") (pintype "bidirectional"))
    )
    (net (code "71") (name "unconnected-(U$1-PB8-PadP45)") (class "Default")
      (node (ref "U$1") (pin "P45") (pinfunction "PB8_P45") (pintype "bidirectional"))
    )
    (net (code "72") (name "unconnected-(U$1-PB9-PadP46)") (class "Default")
      (node (ref "U$1") (pin "P46") (pinfunction "PB9_P46") (pintype "bidirectional"))
    )
    (net (code "73") (name "unconnected-(U$1-PC13-PadP2)") (class "Default")
      (node (ref "U$1") (pin "P2") (pinfunction "PC13_P2") (pintype "bidirectional"))
    )
    (net (code "74") (name "unconnected-(U$1-PC14-PadP3)") (class "Default")
      (node (ref "U$1") (pin "P3") (pinfunction "PC14_P3") (pintype "bidirectional"))
    )
    (net (code "75") (name "unconnected-(U$1-PC15-PadP4)") (class "Default")
      (node (ref "U$1") (pin "P4") (pinfunction "PC15_P4") (pintype "bidirectional"))
    )
    (net (code "76") (name "unconnected-(U$12-IO3-PadP4)") (class "Default")
      (node (ref "U$12") (pin "P4") (pinfunction "IO3_P4") (pintype "bidirectional"))
    )
    (net (code "77") (name "unconnected-(U$12-IO4-PadP6)") (class "Default")
      (node (ref "U$12") (pin "P6") (pinfunction "IO4_P6") (pintype "bidirectional"))
    )
  )
)
